# ajile_ximea_trigger_adapter.net
KiCad netlist of a schematic drawn in EAGLE
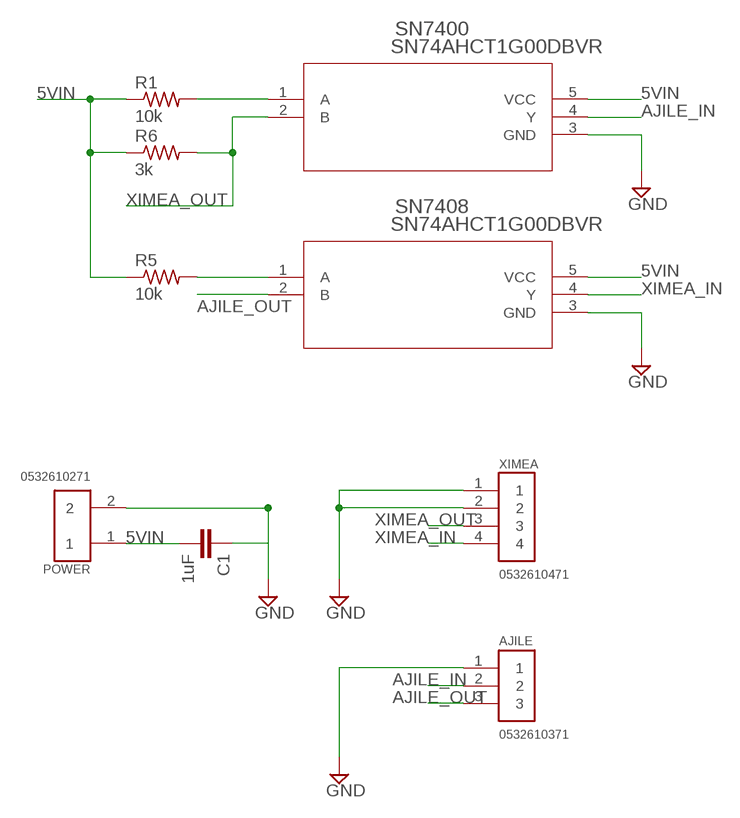
[diagram p0: schematic, sheet 1]

(export (version "E")
  (design (tool "Eeschema 10.0.6"))
  (components
    (comp (ref "AJILE")
      (value "0532610371")
      (footprint "eagle-import:MOLEX_0532610371")
      (fields (field (name "DIGI-KEY_PART_NUMBER") "WM7621CT-ND") (field (name "MF") "Molex, LLC"))
      (libsource (lib "eagle-import") (part "0532610371"))
    )
    (comp (ref "C1")
      (value "1uF")
      (footprint "eagle-import:C0603")
      (libsource (lib "eagle-import") (part "C-EUC0603"))
    )
    (comp (ref "POWER")
      (value "0532610271")
      (footprint "eagle-import:MOLEX_0532610271")
      (fields (field (name "DIGI-KEY_PART_NUMBER") "WM7620CT-ND") (field (name "MF") "Molex, LLC"))
      (libsource (lib "eagle-import") (part "0532610271"))
    )
    (comp (ref "R1")
      (value "10k")
      (footprint "eagle-import:R0603")
      (libsource (lib "eagle-import") (part "R-US_R0603"))
    )
    (comp (ref "R5")
      (value "10k")
      (footprint "eagle-import:R0603")
      (libsource (lib "eagle-import") (part "R-US_R0603"))
    )
    (comp (ref "R6")
      (value "3k")
      (footprint "eagle-import:R0603")
      (libsource (lib "eagle-import") (part "R-US_R0603"))
    )
    (comp (ref "SN7400")
      (value "SN74AHCT1G00DBVR")
      (footprint "eagle-import:DBV5")
      (libsource (lib "eagle-import") (part "SN74AHCT1G00DBVR"))
    )
    (comp (ref "SN7408")
      (value "SN74AHCT1G00DBVR")
      (footprint "eagle-import:DBV5")
      (libsource (lib "eagle-import") (part "SN74AHCT1G00DBVR"))
    )
    (comp (ref "XIMEA")
      (value "0532610471")
      (footprint "eagle-import:MOLEX_0532610471")
      (fields (field (name "DIGI-KEY_PART_NUMBER") "WM7622CT-ND") (field (name "MF") "Molex, LLC"))
      (libsource (lib "eagle-import") (part "0532610471"))
    )
  )
  (nets
    (net (code "1") (name "/5VIN") (class "Default")
      (node (ref "C1") (pin "2") (pinfunction "2_2") (pintype "passive"))
      (node (ref "POWER") (pin "1") (pinfunction "1_1") (pintype "passive"))
      (node (ref "R1") (pin "1") (pinfunction "1_1") (pintype "passive"))
      (node (ref "R5") (pin "1") (pinfunction "1_1") (pintype "passive"))
      (node (ref "R6") (pin "1") (pinfunction "1_1") (pintype "passive"))
      (node (ref "SN7400") (pin "5") (pinfunction "VCC_5") (pintype "power_in"))
      (node (ref "SN7408") (pin "5") (pinfunction "VCC_5") (pintype "power_in"))
    )
    (net (code "2") (name "/AJILE_IN") (class "Default")
      (node (ref "AJILE") (pin "2") (pinfunction "2_2") (pintype "passive"))
      (node (ref "SN7400") (pin "4") (pinfunction "Y_4") (pintype "output"))
    )
    (net (code "3") (name "/AJILE_OUT") (class "Default")
      (node (ref "AJILE") (pin "3") (pinfunction "3_3") (pintype "passive"))
      (node (ref "SN7408") (pin "2") (pinfunction "B_2") (pintype "input"))
    )
    (net (code "4") (name "/XIMEA_IN") (class "Default")
      (node (ref "SN7408") (pin "4") (pinfunction "Y_4") (pintype "output"))
      (node (ref "XIMEA") (pin "4") (pinfunction "4_4") (pintype "passive"))
    )
    (net (code "5") (name "/XIMEA_OUT") (class "Default")
      (node (ref "R6") (pin "2") (pinfunction "2_2") (pintype "passive"))
      (node (ref "SN7400") (pin "2") (pinfunction "B_2") (pintype "input"))
      (node (ref "XIMEA") (pin "3") (pinfunction "3_3") (pintype "passive"))
    )
    (net (code "6") (name "GND") (class "Default")
      (node (ref "AJILE") (pin "1") (pinfunction "1_1") (pintype "passive"))
      (node (ref "C1") (pin "1") (pinfunction "1_1") (pintype "passive"))
      (node (ref "POWER") (pin "2") (pinfunction "2_2") (pintype "passive"))
      (node (ref "SN7400") (pin "3") (pinfunction "GND_3") (pintype "power_in"))
      (node (ref "SN7408") (pin "3") (pinfunction "GND_3") (pintype "power_in"))
      (node (ref "XIMEA") (pin "1") (pinfunction "1_1") (pintype "passive"))
      (node (ref "XIMEA") (pin "2") (pinfunction "2_2") (pintype "passive"))
    )
    (net (code "7") (name "Net-(SN7400-A)") (class "Default")
      (node (ref "R1") (pin "2") (pinfunction "2_2") (pintype "passive"))
      (node (ref "SN7400") (pin "1") (pinfunction "A_1") (pintype "input"))
    )
    (net (code "8") (name "Net-(SN7408-A)") (class "Default")
      (node (ref "R5") (pin "2") (pinfunction "2_2") (pintype "passive"))
      (node (ref "SN7408") (pin "1") (pinfunction "A_1") (pintype "input"))
    )
  )
)
